# led.net
KiCad netlist of a schematic drawn in Altium Designer
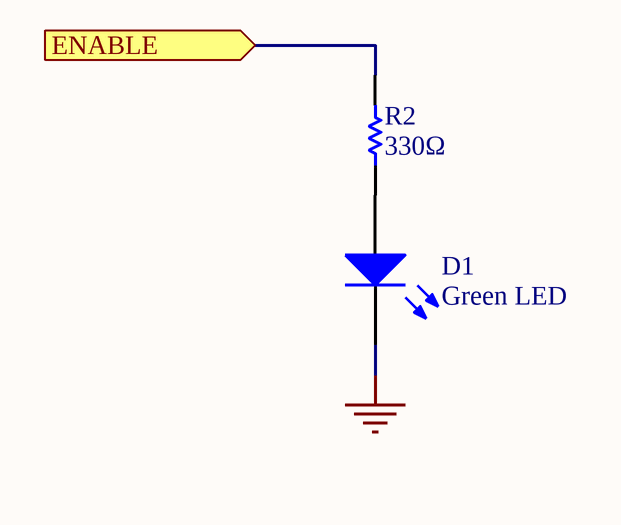
[diagram p0: led.SchDoc]

(export (version "E")
  (design (tool "Eeschema 10.0.6"))
  (components
    (comp (ref "D1")
      (value "Green LED")
      (footprint "LED 0805")
      (description "Typical INFRARED GaAs LED")
      (fields (field (name "PUBLISHER") "Altium Limited"))
      (libsource (lib "Miscellaneous Devices") (part "LED0"))
    )
    (comp (ref "R2")
      (value "330Ω")
      (footprint "RESC1608N")
      (description "Resistor")
      (fields (field (name "PUBLISHER") "Altium Limited"))
      (libsource (lib "Miscellaneous Devices") (part "Res1"))
    )
  )
  (nets
    (net (code "1") (name "/ENABLE") (class "Default")
      (node (ref "R2") (pin "2") (pinfunction "2_2") (pintype "passive"))
    )
    (net (code "2") (name "GND") (class "Default")
      (node (ref "D1") (pin "2") (pinfunction "K_2") (pintype "passive"))
    )
    (net (code "3") (name "Net-(D1-A)") (class "Default")
      (node (ref "D1") (pin "1") (pinfunction "A_1") (pintype "passive"))
      (node (ref "R2") (pin "1") (pinfunction "1_1") (pintype "passive"))
    )
  )
)
